# KSIMU.net
KiCad netlist of a schematic drawn in Altium Designer
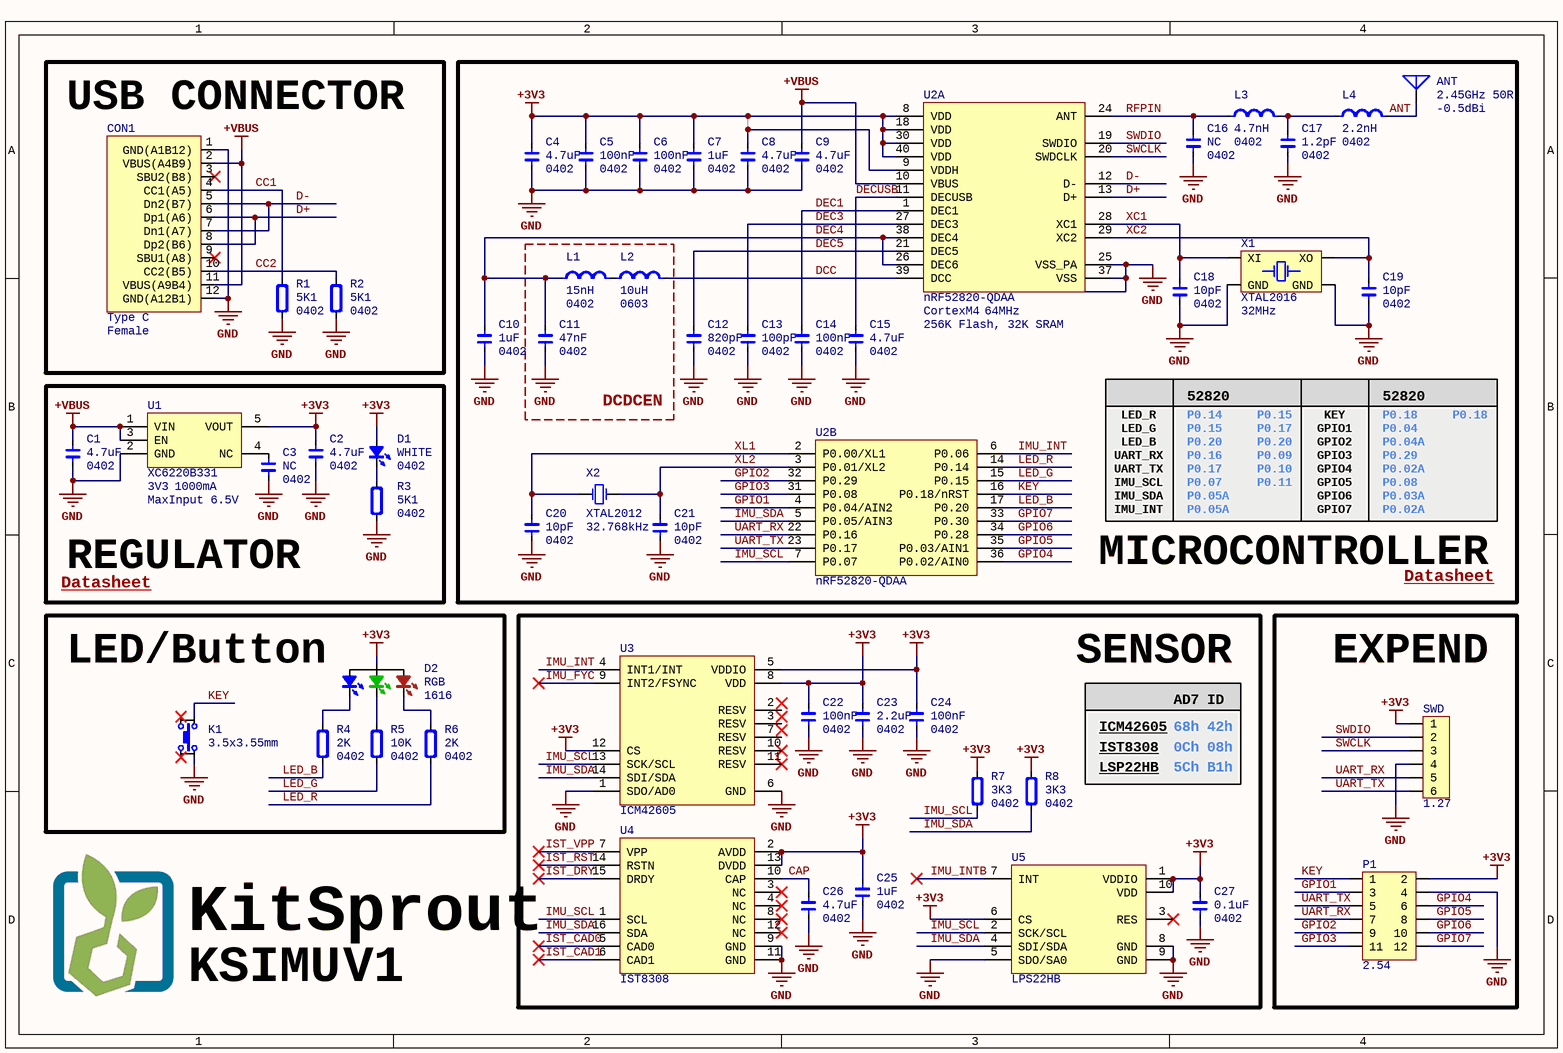
[diagram p0: KSIMU.SchDoc]

(export (version "E")
  (design (tool "Eeschema 10.0.6"))
  (components
    (comp (ref "ANT")
      (value "-0.5dBi")
      (footprint "PCB_Antenna:ANT_2.4G_3.2x1.6")
      (description "Antenna")
      (fields (field (name "SPECIFICATION") "2.45GHz 50R") (field (name "Comment") "2450AT18B100E"))
      (libsource (lib "SCH_Radio") (part "ANT_2.4G"))
    )
    (comp (ref "C1")
      (value "4.7uF")
      (footprint "PCB_Passive:CAP_0402")
      (description "Capacitor")
      (fields (field (name "TYPE") "0402") (field (name "Comment") "C0402"))
      (libsource (lib "SCH_Passive") (part "Cap_0402"))
    )
    (comp (ref "C2")
      (value "4.7uF")
      (footprint "PCB_Passive:CAP_0402")
      (description "Capacitor")
      (fields (field (name "TYPE") "0402") (field (name "Comment") "C0402"))
      (libsource (lib "SCH_Passive") (part "Cap_0402"))
    )
    (comp (ref "C3")
      (value "NC")
      (footprint "PCB_Passive:CAP_0402")
      (description "Capacitor")
      (fields (field (name "TYPE") "0402") (field (name "Comment") "C0402"))
      (libsource (lib "SCH_Passive") (part "Cap_0402"))
    )
    (comp (ref "C4")
      (value "4.7uF")
      (footprint "PCB_Passive:CAP_0402")
      (description "Capacitor")
      (fields (field (name "TYPE") "0402") (field (name "Comment") "C0402"))
      (libsource (lib "SCH_Passive") (part "Cap_0402"))
    )
    (comp (ref "C5")
      (value "100nF")
      (footprint "PCB_Passive:CAP_0402")
      (description "Capacitor")
      (fields (field (name "TYPE") "0402") (field (name "Comment") "C0402"))
      (libsource (lib "SCH_Passive") (part "Cap_0402"))
    )
    (comp (ref "C6")
      (value "100nF")
      (footprint "PCB_Passive:CAP_0402")
      (description "Capacitor")
      (fields (field (name "TYPE") "0402") (field (name "Comment") "C0402"))
      (libsource (lib "SCH_Passive") (part "Cap_0402"))
    )
    (comp (ref "C7")
      (value "1uF")
      (footprint "PCB_Passive:CAP_0402")
      (description "Capacitor")
      (fields (field (name "TYPE") "0402") (field (name "Comment") "C0402"))
      (libsource (lib "SCH_Passive") (part "Cap_0402"))
    )
    (comp (ref "C8")
      (value "4.7uF")
      (footprint "PCB_Passive:CAP_0402")
      (description "Capacitor")
      (fields (field (name "TYPE") "0402") (field (name "Comment") "C0402"))
      (libsource (lib "SCH_Passive") (part "Cap_0402"))
    )
    (comp (ref "C9")
      (value "4.7uF")
      (footprint "PCB_Passive:CAP_0402")
      (description "Capacitor")
      (fields (field (name "TYPE") "0402") (field (name "Comment") "C0402"))
      (libsource (lib "SCH_Passive") (part "Cap_0402"))
    )
    (comp (ref "C10")
      (value "1uF")
      (footprint "PCB_Passive:CAP_0402")
      (description "Capacitor")
      (fields (field (name "TYPE") "0402") (field (name "Comment") "C0402"))
      (libsource (lib "SCH_Passive") (part "Cap_0402"))
    )
    (comp (ref "C11")
      (value "47nF")
      (footprint "PCB_Passive:CAP_0402")
      (description "Capacitor")
      (fields (field (name "TYPE") "0402") (field (name "Comment") "C0402"))
      (libsource (lib "SCH_Passive") (part "Cap_0402"))
    )
    (comp (ref "C12")
      (value "820pF")
      (footprint "PCB_Passive:CAP_0402")
      (description "Capacitor")
      (fields (field (name "TYPE") "0402") (field (name "Comment") "C0402"))
      (libsource (lib "SCH_Passive") (part "Cap_0402"))
    )
    (comp (ref "C13")
      (value "100pF")
      (footprint "PCB_Passive:CAP_0402")
      (description "Capacitor")
      (fields (field (name "TYPE") "0402") (field (name "Comment") "C0402"))
      (libsource (lib "SCH_Passive") (part "Cap_0402"))
    )
    (comp (ref "C14")
      (value "100nF")
      (footprint "PCB_Passive:CAP_0402")
      (description "Capacitor")
      (fields (field (name "TYPE") "0402") (field (name "Comment") "C0402"))
      (libsource (lib "SCH_Passive") (part "Cap_0402"))
    )
    (comp (ref "C15")
      (value "4.7uF")
      (footprint "PCB_Passive:CAP_0402")
      (description "Capacitor")
      (fields (field (name "TYPE") "0402") (field (name "Comment") "C0402"))
      (libsource (lib "SCH_Passive") (part "Cap_0402"))
    )
    (comp (ref "C16")
      (value "NC")
      (footprint "PCB_Passive:CAP_0402")
      (description "Capacitor")
      (fields (field (name "TYPE") "0402") (field (name "Comment") "C0402"))
      (libsource (lib "SCH_Passive") (part "Cap_0402"))
    )
    (comp (ref "C17")
      (value "1.2pF")
      (footprint "PCB_Passive:CAP_0402")
      (description "Capacitor")
      (fields (field (name "TYPE") "0402") (field (name "Comment") "C0402"))
      (libsource (lib "SCH_Passive") (part "Cap_0402"))
    )
    (comp (ref "C18")
      (value "10pF")
      (footprint "PCB_Passive:CAP_0402")
      (description "Capacitor")
      (fields (field (name "TYPE") "0402") (field (name "Comment") "C0402"))
      (libsource (lib "SCH_Passive") (part "Cap_0402"))
    )
    (comp (ref "C19")
      (value "10pF")
      (footprint "PCB_Passive:CAP_0402")
      (description "Capacitor")
      (fields (field (name "TYPE") "0402") (field (name "Comment") "C0402"))
      (libsource (lib "SCH_Passive") (part "Cap_0402"))
    )
    (comp (ref "C20")
      (value "10pF")
      (footprint "PCB_Passive:CAP_0402")
      (description "Capacitor")
      (fields (field (name "TYPE") "0402") (field (name "Comment") "C0402"))
      (libsource (lib "SCH_Passive") (part "Cap_0402"))
    )
    (comp (ref "C21")
      (value "10pF")
      (footprint "PCB_Passive:CAP_0402")
      (description "Capacitor")
      (fields (field (name "TYPE") "0402") (field (name "Comment") "C0402"))
      (libsource (lib "SCH_Passive") (part "Cap_0402"))
    )
    (comp (ref "C22")
      (value "100nF")
      (footprint "PCB_Passive:CAP_0402")
      (description "Capacitor")
      (fields (field (name "TYPE") "0402") (field (name "Comment") "C0402"))
      (libsource (lib "SCH_Passive") (part "Cap_0402"))
    )
    (comp (ref "C23")
      (value "2.2uF")
      (footprint "PCB_Passive:CAP_0402")
      (description "Capacitor")
      (fields (field (name "TYPE") "0402") (field (name "Comment") "C0402"))
      (libsource (lib "SCH_Passive") (part "Cap_0402"))
    )
    (comp (ref "C24")
      (value "100nF")
      (footprint "PCB_Passive:CAP_0402")
      (description "Capacitor")
      (fields (field (name "TYPE") "0402") (field (name "Comment") "C0402"))
      (libsource (lib "SCH_Passive") (part "Cap_0402"))
    )
    (comp (ref "C25")
      (value "1uF")
      (footprint "PCB_Passive:CAP_0402")
      (description "Capacitor")
      (fields (field (name "TYPE") "0402") (field (name "Comment") "C0402"))
      (libsource (lib "SCH_Passive") (part "Cap_0402"))
    )
    (comp (ref "C26")
      (value "4.7uF")
      (footprint "PCB_Passive:CAP_0402")
      (description "Capacitor")
      (fields (field (name "TYPE") "0402") (field (name "Comment") "C0402"))
      (libsource (lib "SCH_Passive") (part "Cap_0402"))
    )
    (comp (ref "C27")
      (value "0.1uF")
      (footprint "PCB_Passive:CAP_0402")
      (description "Capacitor")
      (fields (field (name "TYPE") "0402") (field (name "Comment") "C0402"))
      (libsource (lib "SCH_Passive") (part "Cap_0402"))
    )
    (comp (ref "CON1")
      (value "Type C")
      (footprint "PCB_USB_Connector:USB_TypeC_16P")
      (description "USB TypeC")
      (fields (field (name "TYPE") "Female") (field (name "Comment") "USB Type C"))
      (libsource (lib "SCH_USB_Connector") (part "USB_TypeC_16P_A"))
    )
    (comp (ref "D1")
      (value "WHITE")
      (footprint "PCB_ActiveLED:LED_0402_YELLOW")
      (description "LED")
      (fields (field (name "TYPE") "0402") (field (name "Comment") "D0402"))
      (libsource (lib "SCH_Active") (part "LED_0402"))
    )
    (comp (ref "D2")
      (value "RGB")
      (footprint "PCB_ActiveLED:LED_1616_RGB")
      (description "LED")
      (fields (field (name "TYPE") "1616") (field (name "Comment") "D1616"))
      (libsource (lib "SCH_Active") (part "LED_1616_RGB"))
    )
    (comp (ref "K1")
      (value "TACT")
      (footprint "PCB_Switch:Button_TACT_90_4P_3.5x3.55_H")
      (description "Button")
      (fields (field (name "MANUFACTURER") "Alps Alpine") (field (name "SPECIFICATION") "3.5x3.55mm"))
      (libsource (lib "SCH_Switch") (part "Button_TACT_90_4P_3.5×3.55"))
    )
    (comp (ref "L1")
      (value "15nH")
      (footprint "PCB_Passive:IND_0402")
      (description "Inductor")
      (fields (field (name "TYPE") "0402") (field (name "Comment") "H0402"))
      (libsource (lib "SCH_Passive") (part "Ind_0402"))
    )
    (comp (ref "L2")
      (value "10uH")
      (footprint "PCB_Passive:IND_0603")
      (description "Inductor")
      (fields (field (name "TYPE") "0603") (field (name "Comment") "H0603"))
      (libsource (lib "SCH_Passive") (part "Ind_0603"))
    )
    (comp (ref "L3")
      (value "4.7nH")
      (footprint "PCB_Passive:IND_0402")
      (description "Inductor")
      (fields (field (name "TYPE") "0402") (field (name "Comment") "H0402"))
      (libsource (lib "SCH_Passive") (part "Ind_0402"))
    )
    (comp (ref "L4")
      (value "2.2nH")
      (footprint "PCB_Passive:IND_0402")
      (description "Inductor")
      (fields (field (name "TYPE") "0402") (field (name "Comment") "H0402"))
      (libsource (lib "SCH_Passive") (part "Ind_0402"))
    )
    (comp (ref "P1")
      (value "2.54")
      (footprint "PCB_ConnectorHDR:HDR2X6_2.54_180")
      (description "Header")
      (fields (field (name "Comment") "HDR2x6"))
      (libsource (lib "SCH_ConnectorHDR") (part "HDR2x6_2.54"))
    )
    (comp (ref "R1")
      (value "5K1")
      (footprint "PCB_Passive:RES_0402")
      (description "Resistor")
      (fields (field (name "TYPE") "0402") (field (name "Comment") "R0402"))
      (libsource (lib "SCH_Passive") (part "Res_0402"))
    )
    (comp (ref "R2")
      (value "5K1")
      (footprint "PCB_Passive:RES_0402")
      (description "Resistor")
      (fields (field (name "TYPE") "0402") (field (name "Comment") "R0402"))
      (libsource (lib "SCH_Passive") (part "Res_0402"))
    )
    (comp (ref "R3")
      (value "5K1")
      (footprint "PCB_Passive:RES_0402")
      (description "Resistor")
      (fields (field (name "TYPE") "0402") (field (name "Comment") "R0402"))
      (libsource (lib "SCH_Passive") (part "Res_0402"))
    )
    (comp (ref "R4")
      (value "2K")
      (footprint "PCB_Passive:RES_0402")
      (description "Resistor")
      (fields (field (name "TYPE") "0402") (field (name "Comment") "R0402"))
      (libsource (lib "SCH_Passive") (part "Res_0402"))
    )
    (comp (ref "R5")
      (value "10K")
      (footprint "PCB_Passive:RES_0402")
      (description "Resistor")
      (fields (field (name "TYPE") "0402") (field (name "Comment") "R0402"))
      (libsource (lib "SCH_Passive") (part "Res_0402"))
    )
    (comp (ref "R6")
      (value "2K")
      (footprint "PCB_Passive:RES_0402")
      (description "Resistor")
      (fields (field (name "TYPE") "0402") (field (name "Comment") "R0402"))
      (libsource (lib "SCH_Passive") (part "Res_0402"))
    )
    (comp (ref "R7")
      (value "3K3")
      (footprint "PCB_Passive:RES_0402")
      (description "Resistor")
      (fields (field (name "TYPE") "0402") (field (name "Comment") "R0402"))
      (libsource (lib "SCH_Passive") (part "Res_0402"))
    )
    (comp (ref "R8")
      (value "3K3")
      (footprint "PCB_Passive:RES_0402")
      (description "Resistor")
      (fields (field (name "TYPE") "0402") (field (name "Comment") "R0402"))
      (libsource (lib "SCH_Passive") (part "Res_0402"))
    )
    (comp (ref "SWD")
      (value "1.27")
      (footprint "PCB_ConnectorHDR:HDR1X6_1.27_180F")
      (description "Header")
      (fields (field (name "Comment") "HDR1x6"))
      (libsource (lib "SCH_ConnectorHDR") (part "HDR1x6_1.27"))
    )
    (comp (ref "U1")
      (value "XC6220B331")
      (footprint "PCB_IntegratedCircuit:SOT23-5")
      (description "LDO")
      (fields
        (field (name "ALTIUM_VALUE") "3V3")
        (field (name "MANUFACTURER") "Torex Semiconductor")
        (field (name "SPECIFICATION") "1000mA")
        (field (name "NOTE") "MaxInput 6.5V")
      )
      (libsource (lib "SCH_Power") (part "XC6220x_SOT25"))
    )
    (comp (ref "U2")
      (value "nRF52820-QDAA")
      (footprint "PCB_IntegratedCircuit:QFN40_P0.4_5.0x5.0_H")
      (description "MCU Nordic")
      (fields
        (field (name "ALTIUM_VALUE") "64MHz")
        (field (name "NOTE") "CortexM4")
        (field (name "SPECIFICATION") "256K Flash, 32K SRAM")
        (field (name "MANUFACTURER") "Nordic Semiconductor")
      )
      (libsource (lib "SCH_Microcontroller") (part "nRF52820-QDAA"))
    )
    (comp (ref "U3")
      (value "ICM42605")
      (footprint "PCB_Sensor:ICMx_LGA14_P0.5_2.5x3.0")
      (description "Motion Sensor")
      (fields (field (name "MANUFACTURER") "TDK InvenSense"))
      (libsource (lib "SCH_Sensor") (part "ICM42605"))
    )
    (comp (ref "U4")
      (value "IST8308")
      (footprint "PCB_Sensor:ISTX_LGA16_P0.5_3.0x3.0")
      (description "Magnetometer Sensor")
      (fields (field (name "MANUFACTURER") "iSentek"))
      (libsource (lib "SCH_Sensor") (part "IST8308"))
    )
    (comp (ref "U5")
      (value "LPS22HB")
      (footprint "PCB_Sensor:LPSx_LGA10_P0.5_2.0x2.0")
      (description "Pressure Sensor")
      (fields (field (name "MANUFACTURER") "STMicroelectronics"))
      (libsource (lib "SCH_Sensor") (part "LPS22HB"))
    )
    (comp (ref "X1")
      (value "XTAL2016")
      (footprint "PCB_Oscillator:XT_2016_4")
      (description "Crystal Oscillator")
      (fields (field (name "ALTIUM_VALUE") "32MHz"))
      (libsource (lib "SCH_Oscillator") (part "XTAL_2016_4P"))
    )
    (comp (ref "X2")
      (value "XTAL2012")
      (footprint "PCB_Oscillator:XT_2012_2")
      (description "Crystal Oscillator")
      (fields (field (name "ALTIUM_VALUE") "32.768kHz"))
      (libsource (lib "SCH_Oscillator") (part "XTAL_32.768k_2P"))
    )
  )
  (nets
    (net (code "1") (name "+3V3") (class "Default")
      (node (ref "C2") (pin "2") (pinfunction "2_2") (pintype "passive"))
      (node (ref "C22") (pin "2") (pinfunction "2_2") (pintype "passive"))
      (node (ref "C23") (pin "2") (pinfunction "2_2") (pintype "passive"))
      (node (ref "C24") (pin "2") (pinfunction "2_2") (pintype "passive"))
      (node (ref "C25") (pin "2") (pinfunction "2_2") (pintype "passive"))
      (node (ref "C27") (pin "2") (pinfunction "2_2") (pintype "passive"))
      (node (ref "C4") (pin "2") (pinfunction "2_2") (pintype "passive"))
      (node (ref "C5") (pin "2") (pinfunction "2_2") (pintype "passive"))
      (node (ref "C6") (pin "2") (pinfunction "2_2") (pintype "passive"))
      (node (ref "C7") (pin "2") (pinfunction "2_2") (pintype "passive"))
      (node (ref "C8") (pin "2") (pinfunction "2_2") (pintype "passive"))
      (node (ref "D1") (pin "1") (pinfunction "ANODE_1") (pintype "passive"))
      (node (ref "D2") (pin "3") (pinfunction "ANODE_3") (pintype "passive"))
      (node (ref "P1") (pin "2") (pinfunction "2_2") (pintype "passive"))
      (node (ref "R7") (pin "2") (pinfunction "2_2") (pintype "passive"))
      (node (ref "R8") (pin "2") (pinfunction "2_2") (pintype "passive"))
      (node (ref "SWD") (pin "1") (pinfunction "1_1") (pintype "passive"))
      (node (ref "U1") (pin "5") (pinfunction "VOUT_5") (pintype "passive"))
      (node (ref "U2") (pin "18") (pinfunction "VDD_18") (pintype "passive"))
      (node (ref "U2") (pin "30") (pinfunction "VDD_30") (pintype "passive"))
      (node (ref "U2") (pin "40") (pinfunction "VDD_40") (pintype "passive"))
      (node (ref "U2") (pin "8") (pinfunction "VDD_8") (pintype "passive"))
      (node (ref "U2") (pin "9") (pinfunction "VDDH_9") (pintype "passive"))
      (node (ref "U3") (pin "12") (pinfunction "CS_12") (pintype "passive"))
      (node (ref "U3") (pin "5") (pinfunction "VDDIO_5") (pintype "passive"))
      (node (ref "U3") (pin "8") (pinfunction "VDD_8") (pintype "passive"))
      (node (ref "U4") (pin "13") (pinfunction "DVDD_13") (pintype "passive"))
      (node (ref "U4") (pin "2") (pinfunction "AVDD_2") (pintype "passive"))
      (node (ref "U5") (pin "1") (pinfunction "VDDIO_1") (pintype "passive"))
      (node (ref "U5") (pin "10") (pinfunction "VDD_10") (pintype "passive"))
      (node (ref "U5") (pin "6") (pinfunction "CS_6") (pintype "passive"))
    )
    (net (code "2") (name "+VBUS") (class "Default")
      (node (ref "C1") (pin "2") (pinfunction "2_2") (pintype "passive"))
      (node (ref "C9") (pin "2") (pinfunction "2_2") (pintype "passive"))
      (node (ref "CON1") (pin "11") (pinfunction "VBUS(A9B4)_11") (pintype "passive"))
      (node (ref "CON1") (pin "2") (pinfunction "VBUS(A4B9)_2") (pintype "passive"))
      (node (ref "U1") (pin "1") (pinfunction "VIN_1") (pintype "passive"))
      (node (ref "U1") (pin "3") (pinfunction "EN_3") (pintype "power_in"))
      (node (ref "U2") (pin "10") (pinfunction "VBUS_10") (pintype "passive"))
    )
    (net (code "3") (name "/ANT") (class "Default")
      (node (ref "ANT") (pin "1") (pinfunction "A_1") (pintype "passive"))
      (node (ref "L4") (pin "2") (pinfunction "2_2") (pintype "passive"))
    )
    (net (code "4") (name "/CAP") (class "Default")
      (node (ref "C26") (pin "2") (pinfunction "2_2") (pintype "passive"))
      (node (ref "U4") (pin "10") (pinfunction "CAP_10") (pintype "passive"))
    )
    (net (code "5") (name "/CC1") (class "Default")
      (node (ref "CON1") (pin "4") (pinfunction "CC1(A5)_4") (pintype "passive"))
      (node (ref "R1") (pin "2") (pinfunction "2_2") (pintype "passive"))
    )
    (net (code "6") (name "/CC2") (class "Default")
      (node (ref "CON1") (pin "10") (pinfunction "CC2(B5)_10") (pintype "passive"))
      (node (ref "R2") (pin "2") (pinfunction "2_2") (pintype "passive"))
    )
    (net (code "7") (name "/D+") (class "Default")
      (node (ref "CON1") (pin "6") (pinfunction "Dp1(A6)_6") (pintype "passive"))
      (node (ref "CON1") (pin "8") (pinfunction "Dp2(B6)_8") (pintype "passive"))
      (node (ref "U2") (pin "13") (pinfunction "D+_13") (pintype "passive"))
    )
    (net (code "8") (name "/D-") (class "Default")
      (node (ref "CON1") (pin "5") (pinfunction "Dn2(B7)_5") (pintype "passive"))
      (node (ref "CON1") (pin "7") (pinfunction "Dn1(A7)_7") (pintype "passive"))
      (node (ref "U2") (pin "12") (pinfunction "D-_12") (pintype "passive"))
    )
    (net (code "9") (name "/DCC") (class "Default")
      (node (ref "L2") (pin "2") (pinfunction "2_2") (pintype "passive"))
      (node (ref "U2") (pin "39") (pinfunction "DCC_39") (pintype "passive"))
    )
    (net (code "10") (name "/DEC1") (class "Default")
      (node (ref "C14") (pin "2") (pinfunction "2_2") (pintype "passive"))
      (node (ref "U2") (pin "1") (pinfunction "DEC1_1") (pintype "passive"))
    )
    (net (code "11") (name "/DEC3") (class "Default")
      (node (ref "C13") (pin "2") (pinfunction "2_2") (pintype "passive"))
      (node (ref "U2") (pin "27") (pinfunction "DEC3_27") (pintype "passive"))
    )
    (net (code "12") (name "/DEC4") (class "Default")
      (node (ref "C10") (pin "2") (pinfunction "2_2") (pintype "passive"))
      (node (ref "C11") (pin "2") (pinfunction "2_2") (pintype "passive"))
      (node (ref "L1") (pin "1") (pinfunction "1_1") (pintype "passive"))
      (node (ref "U2") (pin "26") (pinfunction "DEC6_26") (pintype "passive"))
      (node (ref "U2") (pin "38") (pinfunction "DEC4_38") (pintype "passive"))
    )
    (net (code "13") (name "/DEC5") (class "Default")
      (node (ref "C12") (pin "2") (pinfunction "2_2") (pintype "passive"))
      (node (ref "U2") (pin "21") (pinfunction "DEC5_21") (pintype "passive"))
    )
    (net (code "14") (name "/DECUSB") (class "Default")
      (node (ref "C15") (pin "2") (pinfunction "2_2") (pintype "passive"))
      (node (ref "U2") (pin "11") (pinfunction "DECUSB_11") (pintype "passive"))
    )
    (net (code "15") (name "/GPIO1") (class "Default")
      (node (ref "P1") (pin "3") (pinfunction "3_3") (pintype "passive"))
      (node (ref "U2") (pin "4") (pinfunction "P0.04/AIN2_4") (pintype "passive"))
    )
    (net (code "16") (name "/GPIO2") (class "Default")
      (node (ref "P1") (pin "9") (pinfunction "9_9") (pintype "passive"))
      (node (ref "U2") (pin "32") (pinfunction "P0.29_32") (pintype "passive"))
    )
    (net (code "17") (name "/GPIO3") (class "Default")
      (node (ref "P1") (pin "11") (pinfunction "11_11") (pintype "passive"))
      (node (ref "U2") (pin "31") (pinfunction "P0.08_31") (pintype "passive"))
    )
    (net (code "18") (name "/GPIO4") (class "Default")
      (node (ref "P1") (pin "6") (pinfunction "6_6") (pintype "passive"))
      (node (ref "U2") (pin "36") (pinfunction "P0.02/AIN0_36") (pintype "passive"))
    )
    (net (code "19") (name "/GPIO5") (class "Default")
      (node (ref "P1") (pin "8") (pinfunction "8_8") (pintype "passive"))
      (node (ref "U2") (pin "35") (pinfunction "P0.03/AIN1_35") (pintype "passive"))
    )
    (net (code "20") (name "/GPIO6") (class "Default")
      (node (ref "P1") (pin "10") (pinfunction "10_10") (pintype "passive"))
      (node (ref "U2") (pin "34") (pinfunction "P0.28_34") (pintype "passive"))
    )
    (net (code "21") (name "/GPIO7") (class "Default")
      (node (ref "P1") (pin "12") (pinfunction "12_12") (pintype "passive"))
      (node (ref "U2") (pin "33") (pinfunction "P0.30_33") (pintype "passive"))
    )
    (net (code "22") (name "/IMU_FYC") (class "Default")
      (node (ref "U3") (pin "9") (pinfunction "INT2/FSYNC_9") (pintype "passive+no_connect"))
    )
    (net (code "23") (name "/IMU_INT") (class "Default")
      (node (ref "U2") (pin "6") (pinfunction "P0.06_6") (pintype "passive"))
      (node (ref "U3") (pin "4") (pinfunction "INT1/INT_4") (pintype "passive"))
    )
    (net (code "24") (name "/IMU_INTB") (class "Default")
      (node (ref "U5") (pin "7") (pinfunction "INT_7") (pintype "passive+no_connect"))
    )
    (net (code "25") (name "/IMU_SCL") (class "Default")
      (node (ref "R7") (pin "1") (pinfunction "1_1") (pintype "passive"))
      (node (ref "U2") (pin "7") (pinfunction "P0.07_7") (pintype "passive"))
      (node (ref "U3") (pin "13") (pinfunction "SCK/SCL_13") (pintype "passive"))
      (node (ref "U4") (pin "1") (pinfunction "SCL_1") (pintype "passive"))
      (node (ref "U5") (pin "2") (pinfunction "SCK/SCL_2") (pintype "passive"))
    )
    (net (code "26") (name "/IMU_SDA") (class "Default")
      (node (ref "R8") (pin "1") (pinfunction "1_1") (pintype "passive"))
      (node (ref "U2") (pin "5") (pinfunction "P0.05/AIN3_5") (pintype "passive"))
      (node (ref "U3") (pin "14") (pinfunction "SDI/SDA_14") (pintype "passive"))
      (node (ref "U4") (pin "16") (pinfunction "SDA_16") (pintype "passive"))
      (node (ref "U5") (pin "4") (pinfunction "SDI/SDA_4") (pintype "passive"))
    )
    (net (code "27") (name "/IST_CAD0") (class "Default")
      (node (ref "U4") (pin "5") (pinfunction "CAD0_5") (pintype "passive+no_connect"))
    )
    (net (code "28") (name "/IST_CAD1") (class "Default")
      (node (ref "U4") (pin "6") (pinfunction "CAD1_6") (pintype "passive+no_connect"))
    )
    (net (code "29") (name "/IST_DRY") (class "Default")
      (node (ref "U4") (pin "15") (pinfunction "DRDY_15") (pintype "passive+no_connect"))
    )
    (net (code "30") (name "/IST_RST") (class "Default")
      (node (ref "U4") (pin "14") (pinfunction "RSTN_14") (pintype "passive+no_connect"))
    )
    (net (code "31") (name "/IST_VPP") (class "Default")
      (node (ref "U4") (pin "7") (pinfunction "VPP_7") (pintype "passive+no_connect"))
    )
    (net (code "32") (name "/KEY") (class "Default")
      (node (ref "K1") (pin "3") (pinfunction "3_3") (pintype "passive"))
      (node (ref "P1") (pin "1") (pinfunction "1_1") (pintype "passive"))
      (node (ref "U2") (pin "16") (pinfunction "P0.18/nRST_16") (pintype "passive"))
    )
    (net (code "33") (name "/LED_B") (class "Default")
      (node (ref "R4") (pin "1") (pinfunction "1_1") (pintype "passive"))
      (node (ref "U2") (pin "17") (pinfunction "P0.20_17") (pintype "passive"))
    )
    (net (code "34") (name "/LED_G") (class "Default")
      (node (ref "R5") (pin "1") (pinfunction "1_1") (pintype "passive"))
      (node (ref "U2") (pin "15") (pinfunction "P0.15_15") (pintype "passive"))
    )
    (net (code "35") (name "/LED_R") (class "Default")
      (node (ref "R6") (pin "1") (pinfunction "1_1") (pintype "passive"))
      (node (ref "U2") (pin "14") (pinfunction "P0.14_14") (pintype "passive"))
    )
    (net (code "36") (name "/RFPIN") (class "Default")
      (node (ref "C16") (pin "2") (pinfunction "2_2") (pintype "passive"))
      (node (ref "L3") (pin "1") (pinfunction "1_1") (pintype "passive"))
      (node (ref "U2") (pin "24") (pinfunction "ANT_24") (pintype "passive"))
    )
    (net (code "37") (name "/SWCLK") (class "Default")
      (node (ref "SWD") (pin "3") (pinfunction "3_3") (pintype "passive"))
      (node (ref "U2") (pin "20") (pinfunction "SWDCLK_20") (pintype "passive"))
    )
    (net (code "38") (name "/SWDIO") (class "Default")
      (node (ref "SWD") (pin "2") (pinfunction "2_2") (pintype "passive"))
      (node (ref "U2") (pin "19") (pinfunction "SWDIO_19") (pintype "passive"))
    )
    (net (code "39") (name "/UART_RX") (class "Default")
      (node (ref "P1") (pin "7") (pinfunction "7_7") (pintype "passive"))
      (node (ref "SWD") (pin "5") (pinfunction "5_5") (pintype "passive"))
      (node (ref "U2") (pin "22") (pinfunction "P0.16_22") (pintype "passive"))
    )
    (net (code "40") (name "/UART_TX") (class "Default")
      (node (ref "P1") (pin "5") (pinfunction "5_5") (pintype "passive"))
      (node (ref "SWD") (pin "6") (pinfunction "6_6") (pintype "passive"))
      (node (ref "U2") (pin "23") (pinfunction "P0.17_23") (pintype "passive"))
    )
    (net (code "41") (name "/XC1") (class "Default")
      (node (ref "C18") (pin "2") (pinfunction "2_2") (pintype "passive"))
      (node (ref "U2") (pin "28") (pinfunction "XC1_28") (pintype "passive"))
      (node (ref "X1") (pin "1") (pinfunction "XI_1") (pintype "passive"))
    )
    (net (code "42") (name "/XC2") (class "Default")
      (node (ref "C19") (pin "2") (pinfunction "2_2") (pintype "passive"))
      (node (ref "U2") (pin "29") (pinfunction "XC2_29") (pintype "passive"))
      (node (ref "X1") (pin "3") (pinfunction "XO_3") (pintype "passive"))
    )
    (net (code "43") (name "/XL1") (class "Default")
      (node (ref "C20") (pin "2") (pinfunction "2_2") (pintype "passive"))
      (node (ref "U2") (pin "2") (pinfunction "P0.00/XL1_2") (pintype "passive"))
      (node (ref "X2") (pin "1") (pinfunction "OSC1_1") (pintype "passive"))
    )
    (net (code "44") (name "/XL2") (class "Default")
      (node (ref "C21") (pin "2") (pinfunction "2_2") (pintype "passive"))
      (node (ref "U2") (pin "3") (pinfunction "P0.01/XL2_3") (pintype "passive"))
      (node (ref "X2") (pin "2") (pinfunction "OSC2_2") (pintype "passive"))
    )
    (net (code "45") (name "GND") (class "Default")
      (node (ref "C1") (pin "1") (pinfunction "1_1") (pintype "passive"))
      (node (ref "C10") (pin "1") (pinfunction "1_1") (pintype "passive"))
      (node (ref "C11") (pin "1") (pinfunction "1_1") (pintype "passive"))
      (node (ref "C12") (pin "1") (pinfunction "1_1") (pintype "passive"))
      (node (ref "C13") (pin "1") (pinfunction "1_1") (pintype "passive"))
      (node (ref "C14") (pin "1") (pinfunction "1_1") (pintype "passive"))
      (node (ref "C15") (pin "1") (pinfunction "1_1") (pintype "passive"))
      (node (ref "C16") (pin "1") (pinfunction "1_1") (pintype "passive"))
      (node (ref "C17") (pin "1") (pinfunction "1_1") (pintype "passive"))
      (node (ref "C18") (pin "1") (pinfunction "1_1") (pintype "passive"))
      (node (ref "C19") (pin "1") (pinfunction "1_1") (pintype "passive"))
      (node (ref "C2") (pin "1") (pinfunction "1_1") (pintype "passive"))
      (node (ref "C20") (pin "1") (pinfunction "1_1") (pintype "passive"))
      (node (ref "C21") (pin "1") (pinfunction "1_1") (pintype "passive"))
      (node (ref "C22") (pin "1") (pinfunction "1_1") (pintype "passive"))
      (node (ref "C23") (pin "1") (pinfunction "1_1") (pintype "passive"))
      (node (ref "C24") (pin "1") (pinfunction "1_1") (pintype "passive"))
      (node (ref "C25") (pin "1") (pinfunction "1_1") (pintype "passive"))
      (node (ref "C26") (pin "1") (pinfunction "1_1") (pintype "passive"))
      (node (ref "C27") (pin "1") (pinfunction "1_1") (pintype "passive"))
      (node (ref "C3") (pin "1") (pinfunction "1_1") (pintype "passive"))
      (node (ref "C4") (pin "1") (pinfunction "1_1") (pintype "passive"))
      (node (ref "C5") (pin "1") (pinfunction "1_1") (pintype "passive"))
      (node (ref "C6") (pin "1") (pinfunction "1_1") (pintype "passive"))
      (node (ref "C7") (pin "1") (pinfunction "1_1") (pintype "passive"))
      (node (ref "C8") (pin "1") (pinfunction "1_1") (pintype "passive"))
      (node (ref "C9") (pin "1") (pinfunction "1_1") (pintype "passive"))
      (node (ref "CON1") (pin "1") (pinfunction "GND(A1B12)_1") (pintype "passive"))
      (node (ref "CON1") (pin "12") (pinfunction "GND(A12B1)_12") (pintype "passive"))
      (node (ref "K1") (pin "4") (pinfunction "4_4") (pintype "passive"))
      (node (ref "P1") (pin "4") (pinfunction "4_4") (pintype "passive"))
      (node (ref "R1") (pin "1") (pinfunction "1_1") (pintype "passive"))
      (node (ref "R2") (pin "1") (pinfunction "1_1") (pintype "passive"))
      (node (ref "R3") (pin "1") (pinfunction "1_1") (pintype "passive"))
      (node (ref "SWD") (pin "4") (pinfunction "4_4") (pintype "passive"))
      (node (ref "U1") (pin "2") (pinfunction "GND_2") (pintype "passive"))
      (node (ref "U2") (pin "25") (pinfunction "VSS_PA_25") (pintype "passive"))
      (node (ref "U2") (pin "37") (pinfunction "VSS_37") (pintype "passive"))
      (node (ref "U2") (pin "41") (pinfunction "PAD_41") (pintype "passive"))
      (node (ref "U3") (pin "1") (pinfunction "SDO/AD0_1") (pintype "passive"))
      (node (ref "U3") (pin "6") (pinfunction "GND_6") (pintype "passive"))
      (node (ref "U4") (pin "11") (pinfunction "GND_11") (pintype "passive"))
      (node (ref "U4") (pin "9") (pinfunction "GND_9") (pintype "passive"))
      (node (ref "U5") (pin "5") (pinfunction "SDO/SA0_5") (pintype "passive"))
      (node (ref "U5") (pin "8") (pinfunction "GND_8") (pintype "passive"))
      (node (ref "U5") (pin "9") (pinfunction "GND_9") (pintype "passive"))
      (node (ref "X1") (pin "2") (pinfunction "GND_2") (pintype "passive"))
      (node (ref "X1") (pin "4") (pinfunction "GND_4") (pintype "passive"))
    )
    (net (code "46") (name "Net-(C17-Pad2)") (class "Default")
      (node (ref "C17") (pin "2") (pinfunction "2_2") (pintype "passive"))
      (node (ref "L3") (pin "2") (pinfunction "2_2") (pintype "passive"))
      (node (ref "L4") (pin "1") (pinfunction "1_1") (pintype "passive"))
    )
    (net (code "47") (name "Net-(D1-CATHODE)") (class "Default")
      (node (ref "D1") (pin "2") (pinfunction "CATHODE_2") (pintype "passive"))
      (node (ref "R3") (pin "2") (pinfunction "2_2") (pintype "passive"))
    )
    (net (code "48") (name "Net-(D2-CATHODE-Pad1)") (class "Default")
      (node (ref "D2") (pin "1") (pinfunction "CATHODE_1") (pintype "passive"))
      (node (ref "R5") (pin "2") (pinfunction "2_2") (pintype "passive"))
    )
    (net (code "49") (name "Net-(D2-CATHODE-Pad2)") (class "Default")
      (node (ref "D2") (pin "2") (pinfunction "CATHODE_2") (pintype "passive"))
      (node (ref "R4") (pin "2") (pinfunction "2_2") (pintype "passive"))
    )
    (net (code "50") (name "Net-(D2-CATHODE-Pad4)") (class "Default")
      (node (ref "D2") (pin "4") (pinfunction "CATHODE_4") (pintype "passive"))
      (node (ref "R6") (pin "2") (pinfunction "2_2") (pintype "passive"))
    )
    (net (code "51") (name "Net-(L1-Pad2)") (class "Default")
      (node (ref "L1") (pin "2") (pinfunction "2_2") (pintype "passive"))
      (node (ref "L2") (pin "1") (pinfunction "1_1") (pintype "passive"))
    )
    (net (code "52") (name "Net-(U1-NC)") (class "Default")
      (node (ref "C3") (pin "2") (pinfunction "2_2") (pintype "passive"))
      (node (ref "U1") (pin "4") (pinfunction "NC_4") (pintype "passive"))
    )
    (net (code "53") (name "unconnected-(CON1-PadSH)") (class "Default")
      (node (ref "CON1") (pin "SH") (pinfunction "SH_SH") (pintype "passive"))
    )
    (net (code "54") (name "unconnected-(CON1-SBU1(A8)-Pad9)") (class "Default")
      (node (ref "CON1") (pin "9") (pinfunction "SBU1(A8)_9") (pintype "passive+no_connect"))
    )
    (net (code "55") (name "unconnected-(CON1-SBU2(B8)-Pad3)") (class "Default")
      (node (ref "CON1") (pin "3") (pinfunction "SBU2(B8)_3") (pintype "passive+no_connect"))
    )
    (net (code "56") (name "unconnected-(K1-Pad1)") (class "Default")
      (node (ref "K1") (pin "1") (pinfunction "1_1") (pintype "passive+no_connect"))
    )
    (net (code "57") (name "unconnected-(K1-Pad2)") (class "Default")
      (node (ref "K1") (pin "2") (pinfunction "2_2") (pintype "passive+no_connect"))
    )
    (net (code "58") (name "unconnected-(U3-RESV-Pad2)") (class "Default")
      (node (ref "U3") (pin "2") (pinfunction "RESV_2") (pintype "passive"))
    )
    (net (code "59") (name "unconnected-(U3-RESV-Pad3)") (class "Default")
      (node (ref "U3") (pin "3") (pinfunction "RESV_3") (pintype "passive"))
    )
    (net (code "60") (name "unconnected-(U3-RESV-Pad7)") (class "Default")
      (node (ref "U3") (pin "7") (pinfunction "RESV_7") (pintype "passive"))
    )
    (net (code "61") (name "unconnected-(U3-RESV-Pad10)") (class "Default")
      (node (ref "U3") (pin "10") (pinfunction "RESV_10") (pintype "passive+no_connect"))
    )
    (net (code "62") (name "unconnected-(U3-RESV-Pad11)") (class "Default")
      (node (ref "U3") (pin "11") (pinfunction "RESV_11") (pintype "passive+no_connect"))
    )
    (net (code "63") (name "unconnected-(U4-NC-Pad3)") (class "Default")
      (node (ref "U4") (pin "3") (pinfunction "NC_3") (pintype "passive+no_connect"))
    )
    (net (code "64") (name "unconnected-(U4-NC-Pad4)") (class "Default")
      (node (ref "U4") (pin "4") (pinfunction "NC_4") (pintype "passive+no_connect"))
    )
    (net (code "65") (name "unconnected-(U4-NC-Pad8)") (class "Default")
      (node (ref "U4") (pin "8") (pinfunction "NC_8") (pintype "passive+no_connect"))
    )
    (net (code "66") (name "unconnected-(U4-NC-Pad12)") (class "Default")
      (node (ref "U4") (pin "12") (pinfunction "NC_12") (pintype "passive+no_connect"))
    )
    (net (code "67") (name "unconnected-(U5-RES-Pad3)") (class "Default")
      (node (ref "U5") (pin "3") (pinfunction "RES_3") (pintype "passive+no_connect"))
    )
  )
)
